# RAUPS_SingleLayer_Heater.net
KiCad netlist of a schematic drawn in EAGLE
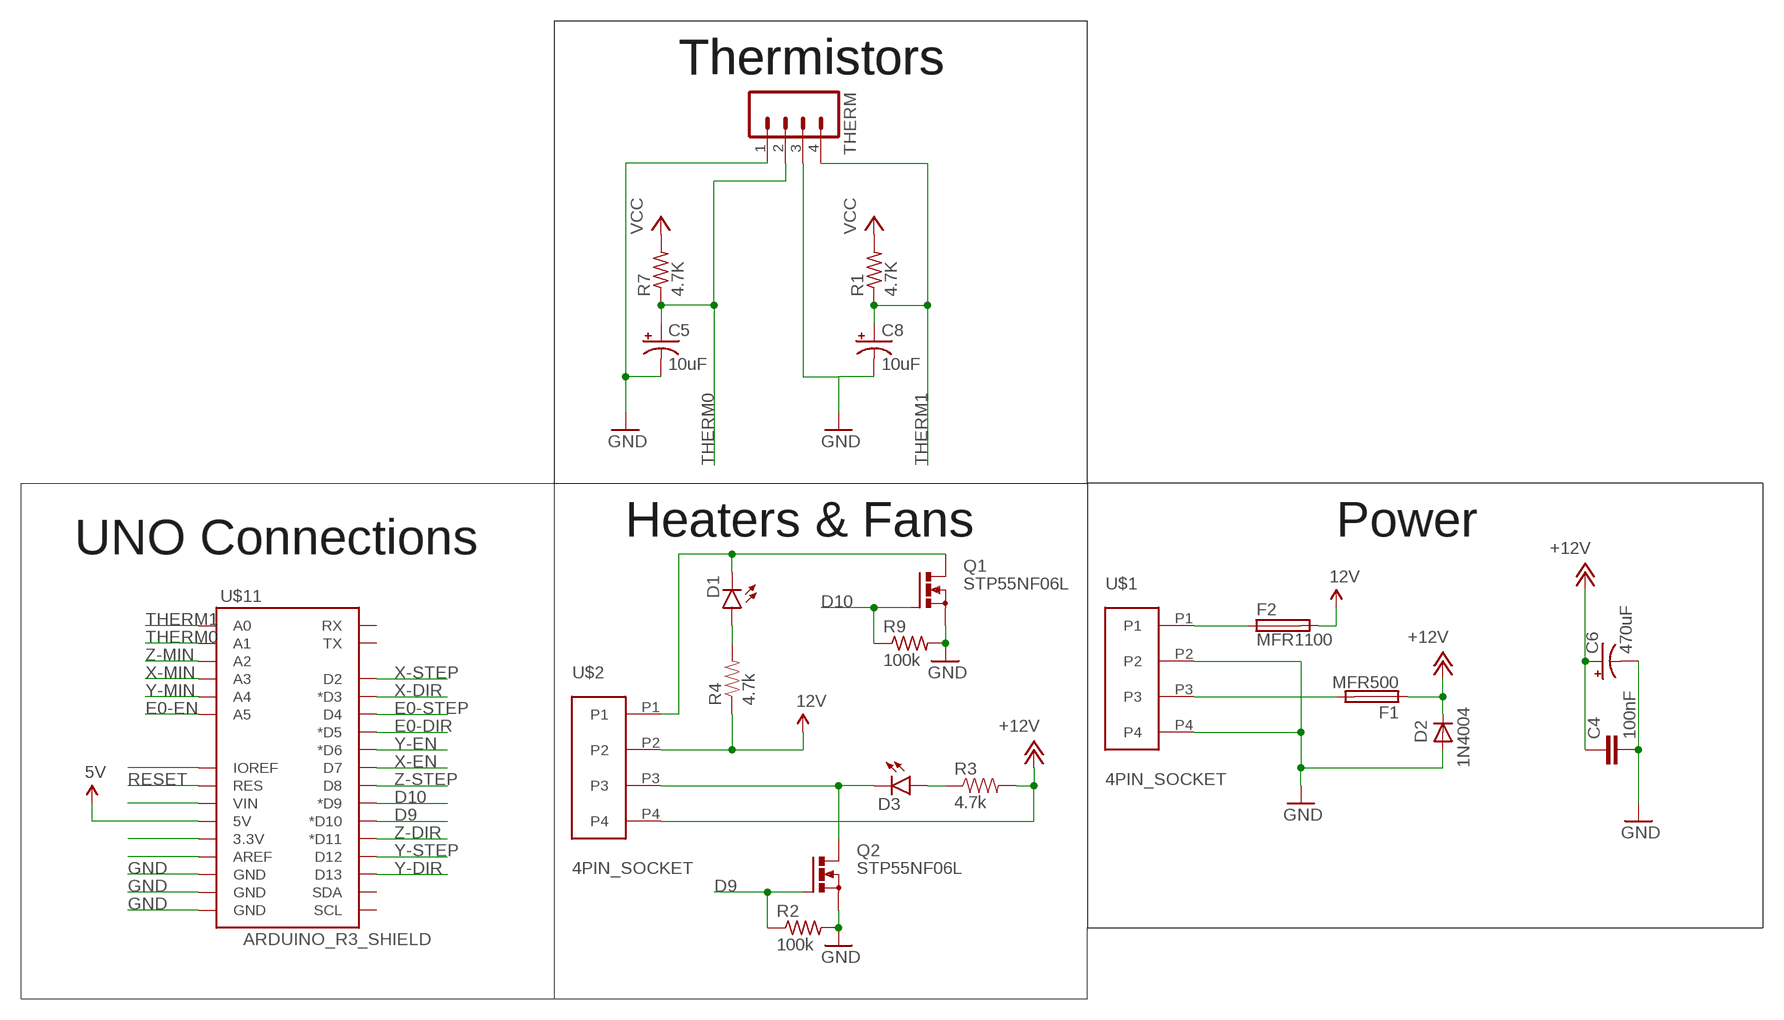
[diagram p0: schematic, sheet 1]

(export (version "E")
  (design (tool "Eeschema 10.0.6"))
  (components
    (comp (ref "C4")
      (value "100nF")
      (footprint "eagle-import:C2.5-3")
      (libsource (lib "eagle-import") (part "C2,5-3"))
    )
    (comp (ref "C5")
      (value "10uF")
      (footprint "eagle-import:E2,5-5")
      (libsource (lib "eagle-import") (part "CPOL-USE2.5-5"))
    )
    (comp (ref "C6")
      (value "470uF")
      (footprint "eagle-import:E3,5-8")
      (libsource (lib "eagle-import") (part "CPOL-USE3.5-8"))
    )
    (comp (ref "C8")
      (value "10uF")
      (footprint "eagle-import:E2,5-5")
      (libsource (lib "eagle-import") (part "CPOL-USE2.5-5"))
    )
    (comp (ref "D1")
      (value "LED-3MM-NO_SILK")
      (footprint "eagle-import:LED3MM-NS")
      (libsource (lib "eagle-import") (part "LED-3MM-NO_SILK"))
    )
    (comp (ref "D2")
      (value "1N4004")
      (footprint "eagle-import:DO41-10")
      (libsource (lib "eagle-import") (part "1N4004"))
    )
    (comp (ref "D3")
      (value "LED-3MM-NO_SILK")
      (footprint "eagle-import:LED3MM-NS")
      (libsource (lib "eagle-import") (part "LED-3MM-NO_SILK"))
    )
    (comp (ref "F1")
      (value "MFR500")
      (footprint "eagle-import:MFR500")
      (libsource (lib "eagle-import") (part "PTCFUSE"))
    )
    (comp (ref "F2")
      (value "MFR1100")
      (footprint "eagle-import:MFR1100")
      (libsource (lib "eagle-import") (part "PTCFUSEMFR1100"))
    )
    (comp (ref "Q1")
      (value "STP55NF06L")
      (footprint "eagle-import:TO220BV")
      (libsource (lib "eagle-import") (part "IRF512"))
    )
    (comp (ref "Q2")
      (value "STP55NF06L")
      (footprint "eagle-import:TO220BV")
      (libsource (lib "eagle-import") (part "IRF512"))
    )
    (comp (ref "R1")
      (value "4.7K")
      (footprint "eagle-import:0207_7")
      (libsource (lib "eagle-import") (part "R-US_0207/7"))
    )
    (comp (ref "R2")
      (value "100k")
      (footprint "eagle-import:0207_7")
      (libsource (lib "eagle-import") (part "R-US_0207/7"))
    )
    (comp (ref "R3")
      (value "4.7k")
      (footprint "eagle-import:AXIAL-0.3")
      (libsource (lib "eagle-import") (part "1KOHM-1/4W-5%(PTH)"))
    )
    (comp (ref "R4")
      (value "4.7k")
      (footprint "eagle-import:AXIAL-0.3")
      (libsource (lib "eagle-import") (part "1KOHM-1/4W-5%(PTH)"))
    )
    (comp (ref "R7")
      (value "4.7K")
      (footprint "eagle-import:0207_7")
      (libsource (lib "eagle-import") (part "R-US_0207/7"))
    )
    (comp (ref "R9")
      (value "100k")
      (footprint "eagle-import:0207_7")
      (libsource (lib "eagle-import") (part "R-US_0207/7"))
    )
    (comp (ref "THERM")
      (value "M04LONGPADS")
      (footprint "eagle-import:1X04_LONGPADS")
      (libsource (lib "eagle-import") (part "M04LONGPADS"))
    )
    (comp (ref "U$1")
      (value "4PIN_SOCKET")
      (footprint "eagle-import:CONN-4PIN")
      (libsource (lib "eagle-import") (part "4PIN_SOCKET"))
    )
    (comp (ref "U$2")
      (value "4PIN_SOCKET")
      (footprint "eagle-import:CONN-4PIN")
      (libsource (lib "eagle-import") (part "4PIN_SOCKET"))
    )
    (comp (ref "U$11")
      (value "ARDUINO_R3_SHIELD")
      (footprint "eagle-import:UNO_R3_SHIELD")
      (libsource (lib "eagle-import") (part "ARDUINO_R3_SHIELD"))
    )
  )
  (nets
    (net (code "1") (name "+12V") (class "Default")
      (node (ref "C4") (pin "1") (pinfunction "1_1") (pintype "passive"))
      (node (ref "C6") (pin "+") (pinfunction "+_+") (pintype "passive"))
      (node (ref "D2") (pin "C") (pinfunction "C_C") (pintype "passive"))
      (node (ref "F1") (pin "1") (pinfunction "1_1") (pintype "passive"))
      (node (ref "R3") (pin "P$2") (pinfunction "2_P$2") (pintype "passive"))
      (node (ref "U$2") (pin "P4") (pinfunction "P4_P4") (pintype "bidirectional"))
    )
    (net (code "2") (name "/D9") (class "Default")
      (node (ref "Q2") (pin "G") (pinfunction "G_G") (pintype "passive"))
      (node (ref "R2") (pin "1") (pinfunction "1_1") (pintype "passive"))
      (node (ref "U$11") (pin "D10") (pinfunction "*D10_D10") (pintype "bidirectional"))
    )
    (net (code "3") (name "/D10") (class "Default")
      (node (ref "Q1") (pin "G") (pinfunction "G_G") (pintype "passive"))
      (node (ref "R9") (pin "1") (pinfunction "1_1") (pintype "passive"))
      (node (ref "U$11") (pin "D9") (pinfunction "*D9_D9") (pintype "bidirectional"))
    )
    (net (code "4") (name "/E0-DIR") (class "Default")
      (node (ref "U$11") (pin "D5") (pinfunction "*D5_D5") (pintype "bidirectional"))
    )
    (net (code "5") (name "/E0-EN") (class "Default")
      (node (ref "U$11") (pin "A5") (pinfunction "A5_A5") (pintype "bidirectional"))
    )
    (net (code "6") (name "/E0-STEP") (class "Default")
      (node (ref "U$11") (pin "D4") (pinfunction "D4_D4") (pintype "bidirectional"))
    )
    (net (code "7") (name "/RESET") (class "Default")
      (node (ref "U$11") (pin "RES") (pinfunction "RES_RES") (pintype "bidirectional"))
    )
    (net (code "8") (name "/THERM0") (class "Default")
      (node (ref "C5") (pin "+") (pinfunction "+_+") (pintype "passive"))
      (node (ref "R7") (pin "1") (pinfunction "1_1") (pintype "passive"))
      (node (ref "THERM") (pin "2") (pinfunction "2_2") (pintype "passive"))
      (node (ref "U$11") (pin "A1") (pinfunction "A1_A1") (pintype "bidirectional"))
    )
    (net (code "9") (name "/THERM1") (class "Default")
      (node (ref "C8") (pin "+") (pinfunction "+_+") (pintype "passive"))
      (node (ref "R1") (pin "1") (pinfunction "1_1") (pintype "passive"))
      (node (ref "THERM") (pin "4") (pinfunction "4_4") (pintype "passive"))
      (node (ref "U$11") (pin "A0") (pinfunction "A0_A0") (pintype "bidirectional"))
    )
    (net (code "10") (name "/X-DIR") (class "Default")
      (node (ref "U$11") (pin "D3") (pinfunction "*D3_D3") (pintype "bidirectional"))
    )
    (net (code "11") (name "/X-EN") (class "Default")
      (node (ref "U$11") (pin "D7") (pinfunction "D7_D7") (pintype "bidirectional"))
    )
    (net (code "12") (name "/X-MIN") (class "Default")
      (node (ref "U$11") (pin "A3") (pinfunction "A3_A3") (pintype "bidirectional"))
    )
    (net (code "13") (name "/X-STEP") (class "Default")
      (node (ref "U$11") (pin "D2") (pinfunction "D2_D2") (pintype "bidirectional"))
    )
    (net (code "14") (name "/Y-DIR") (class "Default")
      (node (ref "U$11") (pin "D13") (pinfunction "D13_D13") (pintype "bidirectional"))
    )
    (net (code "15") (name "/Y-EN") (class "Default")
      (node (ref "U$11") (pin "D6") (pinfunction "*D6_D6") (pintype "bidirectional"))
    )
    (net (code "16") (name "/Y-MIN") (class "Default")
      (node (ref "U$11") (pin "A4") (pinfunction "A4_A4") (pintype "bidirectional"))
    )
    (net (code "17") (name "/Y-STEP") (class "Default")
      (node (ref "U$11") (pin "D12") (pinfunction "D12_D12") (pintype "bidirectional"))
    )
    (net (code "18") (name "/Z-DIR") (class "Default")
      (node (ref "U$11") (pin "D11") (pinfunction "*D11_D11") (pintype "bidirectional"))
    )
    (net (code "19") (name "/Z-MIN") (class "Default")
      (node (ref "U$11") (pin "A2") (pinfunction "A2_A2") (pintype "bidirectional"))
    )
    (net (code "20") (name "/Z-STEP") (class "Default")
      (node (ref "U$11") (pin "D8") (pinfunction "D8_D8") (pintype "bidirectional"))
    )
    (net (code "21") (name "5V") (class "Default")
      (node (ref "U$11") (pin "5V") (pinfunction "5V_5V") (pintype "bidirectional"))
    )
    (net (code "22") (name "12V") (class "Default")
      (node (ref "F2") (pin "2") (pinfunction "2_2") (pintype "passive"))
      (node (ref "R4") (pin "P$1") (pinfunction "1_P$1") (pintype "passive"))
      (node (ref "U$2") (pin "P2") (pinfunction "P2_P2") (pintype "bidirectional"))
    )
    (net (code "23") (name "GND") (class "Default")
      (node (ref "C4") (pin "2") (pinfunction "2_2") (pintype "passive"))
      (node (ref "C5") (pin "-") (pinfunction "-_-") (pintype "passive"))
      (node (ref "C6") (pin "-") (pinfunction "-_-") (pintype "passive"))
      (node (ref "C8") (pin "-") (pinfunction "-_-") (pintype "passive"))
      (node (ref "D2") (pin "A") (pinfunction "A_A") (pintype "passive"))
      (node (ref "Q1") (pin "S") (pinfunction "S_S") (pintype "passive"))
      (node (ref "Q2") (pin "S") (pinfunction "S_S") (pintype "passive"))
      (node (ref "R2") (pin "2") (pinfunction "2_2") (pintype "passive"))
      (node (ref "R9") (pin "2") (pinfunction "2_2") (pintype "passive"))
      (node (ref "THERM") (pin "1") (pinfunction "1_1") (pintype "passive"))
      (node (ref "THERM") (pin "3") (pinfunction "3_3") (pintype "passive"))
      (node (ref "U$1") (pin "P2") (pinfunction "P2_P2") (pintype "bidirectional"))
      (node (ref "U$1") (pin "P4") (pinfunction "P4_P4") (pintype "bidirectional"))
      (node (ref "U$11") (pin "GND@0") (pinfunction "GND_GND@0") (pintype "bidirectional"))
      (node (ref "U$11") (pin "GND@1") (pinfunction "GND_GND@1") (pintype "bidirectional"))
      (node (ref "U$11") (pin "GND@2") (pinfunction "GND_GND@2") (pintype "bidirectional"))
    )
    (net (code "24") (name "Net-(D1-C)") (class "Default")
      (node (ref "D1") (pin "K") (pinfunction "C_K") (pintype "passive"))
      (node (ref "Q1") (pin "D") (pinfunction "D_D") (pintype "passive"))
      (node (ref "U$2") (pin "P1") (pinfunction "P1_P1") (pintype "bidirectional"))
    )
    (net (code "25") (name "Net-(D3-C)") (class "Default")
      (node (ref "D3") (pin "K") (pinfunction "C_K") (pintype "passive"))
      (node (ref "Q2") (pin "D") (pinfunction "D_D") (pintype "passive"))
      (node (ref "U$2") (pin "P3") (pinfunction "P3_P3") (pintype "bidirectional"))
    )
    (net (code "26") (name "Net-(F1-Pad2)") (class "Default")
      (node (ref "F1") (pin "2") (pinfunction "2_2") (pintype "passive"))
      (node (ref "U$1") (pin "P3") (pinfunction "P3_P3") (pintype "bidirectional"))
    )
    (net (code "27") (name "Net-(F2-Pad1)") (class "Default")
      (node (ref "F2") (pin "1") (pinfunction "1_1") (pintype "passive"))
      (node (ref "U$1") (pin "P1") (pinfunction "P1_P1") (pintype "bidirectional"))
    )
    (net (code "28") (name "Net-(R3-1)") (class "Default")
      (node (ref "D3") (pin "A") (pinfunction "A_A") (pintype "passive"))
      (node (ref "R3") (pin "P$1") (pinfunction "1_P$1") (pintype "passive"))
    )
    (net (code "29") (name "Net-(R4-2)") (class "Default")
      (node (ref "D1") (pin "A") (pinfunction "A_A") (pintype "passive"))
      (node (ref "R4") (pin "P$2") (pinfunction "2_P$2") (pintype "passive"))
    )
    (net (code "30") (name "VCC") (class "Default")
      (node (ref "R1") (pin "2") (pinfunction "2_2") (pintype "passive"))
      (node (ref "R7") (pin "2") (pinfunction "2_2") (pintype "passive"))
    )
    (net (code "31") (name "unconnected-(U$11-Pad3.3V)") (class "Default")
      (node (ref "U$11") (pin "3.3V") (pinfunction "3.3V_3.3V") (pintype "bidirectional"))
    )
    (net (code "32") (name "unconnected-(U$11-PadAREF)") (class "Default")
      (node (ref "U$11") (pin "AREF") (pinfunction "AREF_AREF") (pintype "bidirectional"))
    )
    (net (code "33") (name "unconnected-(U$11-PadIOREF)") (class "Default")
      (node (ref "U$11") (pin "IOREF") (pinfunction "IOREF_IOREF") (pintype "bidirectional"))
    )
    (net (code "34") (name "unconnected-(U$11-PadRX)") (class "Default")
      (node (ref "U$11") (pin "RX") (pinfunction "RX_RX") (pintype "bidirectional"))
    )
    (net (code "35") (name "unconnected-(U$11-PadSCL)") (class "Default")
      (node (ref "U$11") (pin "SCL") (pinfunction "SCL_SCL") (pintype "bidirectional"))
    )
    (net (code "36") (name "unconnected-(U$11-PadSDA)") (class "Default")
      (node (ref "U$11") (pin "SDA") (pinfunction "SDA_SDA") (pintype "bidirectional"))
    )
    (net (code "37") (name "unconnected-(U$11-PadTX)") (class "Default")
      (node (ref "U$11") (pin "TX") (pinfunction "TX_TX") (pintype "bidirectional"))
    )
    (net (code "38") (name "unconnected-(U$11-PadVIN)") (class "Default")
      (node (ref "U$11") (pin "VIN") (pinfunction "VIN_VIN") (pintype "bidirectional"))
    )
  )
)
